# Power_Supply.net
KiCad netlist of a schematic drawn in Altium Designer
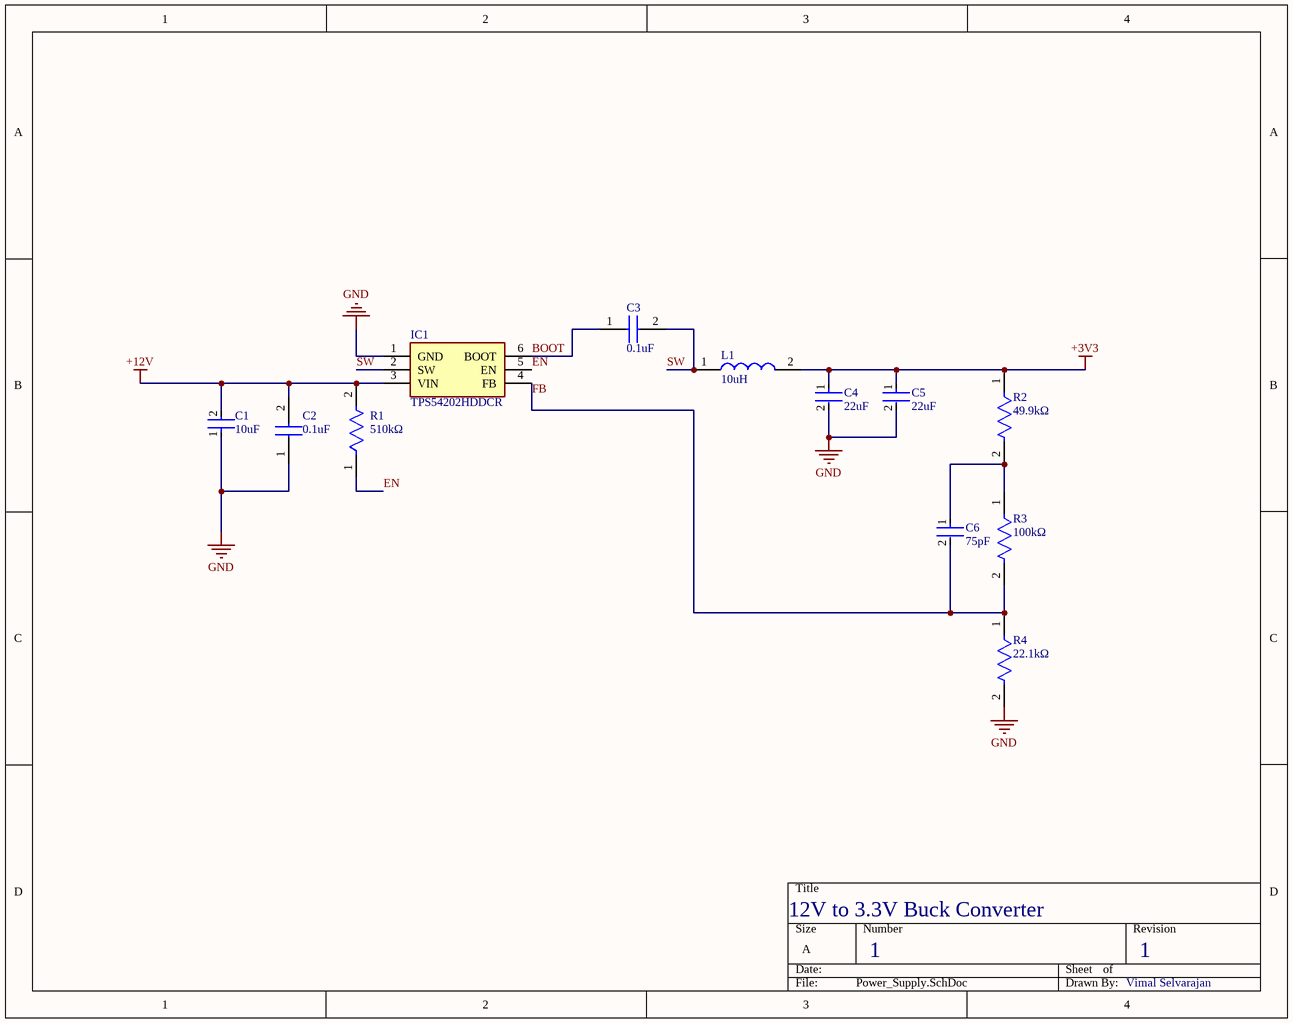
[diagram p0: Power_Supply.SchDoc]

(export (version "E")
  (design (tool "Eeschema 10.0.6"))
  (components
    (comp (ref "C1")
      (value "10uF")
      (footprint "FP-GRT31C-0_2-IPC_A")
      (description "Multi-Layer Ceramic Capacitor 10uF 50V X5R ±10% 1206 Emboss T/R")
      (fields (field (name "TOLERANCE") "10%"))
      (libsource (lib "Altium Content Vault") (part "02cd4be3c70576c341d710602a673aa"))
    )
    (comp (ref "C2")
      (value "0.1uF")
      (footprint "SamacSys:C0805")
      (description "Capacitor")
      (fields
        (field (name "MANUFACTURER_PART_NUMBER") "C0805C104K6RACTU")
        (field (name "MOUSER PART NUMBER") "80-C0805C104K6R")
      )
      (libsource (lib "*") (part "C0805C104K6RACTU"))
    )
    (comp (ref "C3")
      (value "0.1uF")
      (footprint "SamacSys:C0805")
      (description "Capacitor")
      (fields
        (field (name "MANUFACTURER_PART_NUMBER") "C0805C104K6RACTU")
        (field (name "MOUSER PART NUMBER") "80-C0805C104K6R")
      )
      (libsource (lib "*") (part "C0805C104K6RACTU"))
    )
    (comp (ref "C4")
      (value "22uF")
      (footprint "FP-1206-L_3_2_0_3-W_1_6_0-IPC_A")
      (description "None")
      (fields (field (name "TOLERANCE") "20%"))
      (libsource (lib "Altium Content Vault") (part "11868f565c42a9108669ba33697ecf6"))
    )
    (comp (ref "C5")
      (value "22uF")
      (footprint "FP-1206-L_3_2_0_3-W_1_6_0-IPC_A")
      (description "None")
      (fields (field (name "TOLERANCE") "20%"))
      (libsource (lib "Altium Content Vault") (part "11868f565c42a9108669ba33697ecf6"))
    )
    (comp (ref "C6")
      (value "75pF")
      (footprint "FP-C1206C-EB-MFG")
      (description "CAP CER 75PF 50V NP0 1206")
      (fields (field (name "TOLERANCE") "0.05") (field (name "MANUFACTURER PART NUMBER") "C1206C750J5GACTU"))
      (libsource (lib "Altium Content Vault") (part "b4654b650e69147ec39a6b967a45e02"))
    )
    (comp (ref "IC1")
      (value "TPS54202HDDCR")
      (footprint "SamacSys:SOT95P280X110-6N")
      (description "Integrated Circuit")
      (fields (field (name "MOUSER PART NUMBER") "595-TPS54202HDDCR"))
      (libsource (lib "*") (part "TPS54202HDDCR"))
    )
    (comp (ref "L1")
      (value "10uH")
      (footprint "SamacSys:SRN6045_1")
      (description "Inductor")
      (fields
        (field (name "MANUFACTURER_PART_NUMBER") "SRN6045-100M")
        (field (name "MOUSER PART NUMBER") "652-SRN6045-100M")
      )
      (libsource (lib "*") (part "SRN6045-100M"))
    )
    (comp (ref "R1")
      (value "510kΩ")
      (footprint "FP-CRCW0805-e3-IPC_B")
      (description "RES Thick Film, 510kΩ, 1%, 0.125W, 100ppm/°C, 0805")
      (fields (field (name "TOLERANCE") "1%"))
      (libsource (lib "Altium Content Vault") (part "1029c3af85768c4190bb7ad29bc67b5"))
    )
    (comp (ref "R2")
      (value "49.9kΩ")
      (footprint "FP-CRCW0805-e3-IPC_C")
      (description "RES Thick Film, 49.9kΩ, 1%, 0.125W, 100ppm/°C, 0805")
      (fields (field (name "TOLERANCE") "1%"))
      (libsource (lib "Altium Content Vault") (part "1029c3af85768c4190bb7ad29bc67b5"))
    )
    (comp (ref "R3")
      (value "100kΩ")
      (footprint "FP-CRCW0805-e3-MFG")
      (description "RES Thick Film, 100kΩ, 1%, 0.125W, 100ppm/°C, 0805")
      (fields (field (name "TOLERANCE") "1%"))
      (libsource (lib "Altium Content Vault") (part "1029c3af85768c4190bb7ad29bc67b5"))
    )
    (comp (ref "R4")
      (value "22.1kΩ")
      (footprint "FP-CRCW0805-e3-IPC_C")
      (description "RES Thick Film, 22.1kΩ, 1%, 0.125W, 100ppm/°C, 0805")
      (fields (field (name "TOLERANCE") "1%"))
      (libsource (lib "Altium Content Vault") (part "1029c3af85768c4190bb7ad29bc67b5"))
    )
  )
  (nets
    (net (code "1") (name "+3V3") (class "Default")
      (node (ref "C4") (pin "1") (pinfunction "1_1") (pintype "passive"))
      (node (ref "C5") (pin "1") (pinfunction "1_1") (pintype "passive"))
      (node (ref "L1") (pin "2") (pinfunction "2_2") (pintype "passive"))
      (node (ref "R2") (pin "1") (pinfunction "1_1") (pintype "passive"))
    )
    (net (code "2") (name "+12V") (class "Default")
      (node (ref "C1") (pin "2") (pinfunction "2_2") (pintype "passive"))
      (node (ref "C2") (pin "2") (pinfunction "2_2") (pintype "passive"))
      (node (ref "IC1") (pin "3") (pinfunction "VIN_3") (pintype "passive"))
      (node (ref "R1") (pin "2") (pinfunction "2_2") (pintype "passive"))
    )
    (net (code "3") (name "/BOOT") (class "Default")
      (node (ref "C3") (pin "1") (pinfunction "1_1") (pintype "passive"))
      (node (ref "IC1") (pin "6") (pinfunction "BOOT_6") (pintype "passive"))
    )
    (net (code "4") (name "/EN") (class "Default")
      (node (ref "IC1") (pin "5") (pinfunction "EN_5") (pintype "passive"))
      (node (ref "R1") (pin "1") (pinfunction "1_1") (pintype "passive"))
    )
    (net (code "5") (name "/FB") (class "Default")
      (node (ref "C6") (pin "2") (pinfunction "2_2") (pintype "passive"))
      (node (ref "IC1") (pin "4") (pinfunction "FB_4") (pintype "passive"))
      (node (ref "R3") (pin "2") (pinfunction "2_2") (pintype "passive"))
      (node (ref "R4") (pin "1") (pinfunction "1_1") (pintype "passive"))
    )
    (net (code "6") (name "/SW") (class "Default")
      (node (ref "C3") (pin "2") (pinfunction "2_2") (pintype "passive"))
      (node (ref "IC1") (pin "2") (pinfunction "SW_2") (pintype "passive"))
      (node (ref "L1") (pin "1") (pinfunction "1_1") (pintype "passive"))
    )
    (net (code "7") (name "GND") (class "Default")
      (node (ref "C1") (pin "1") (pinfunction "1_1") (pintype "passive"))
      (node (ref "C2") (pin "1") (pinfunction "1_1") (pintype "passive"))
      (node (ref "C4") (pin "2") (pinfunction "2_2") (pintype "passive"))
      (node (ref "C5") (pin "2") (pinfunction "2_2") (pintype "passive"))
      (node (ref "IC1") (pin "1") (pinfunction "GND_1") (pintype "passive"))
      (node (ref "R4") (pin "2") (pinfunction "2_2") (pintype "passive"))
    )
    (net (code "8") (name "Net-(C6-Pad1)") (class "Default")
      (node (ref "C6") (pin "1") (pinfunction "1_1") (pintype "passive"))
      (node (ref "R2") (pin "2") (pinfunction "2_2") (pintype "passive"))
      (node (ref "R3") (pin "1") (pinfunction "1_1") (pintype "passive"))
    )
  )
)
